# stlinkv2_1.net
KiCad netlist of a schematic drawn in Altium Designer
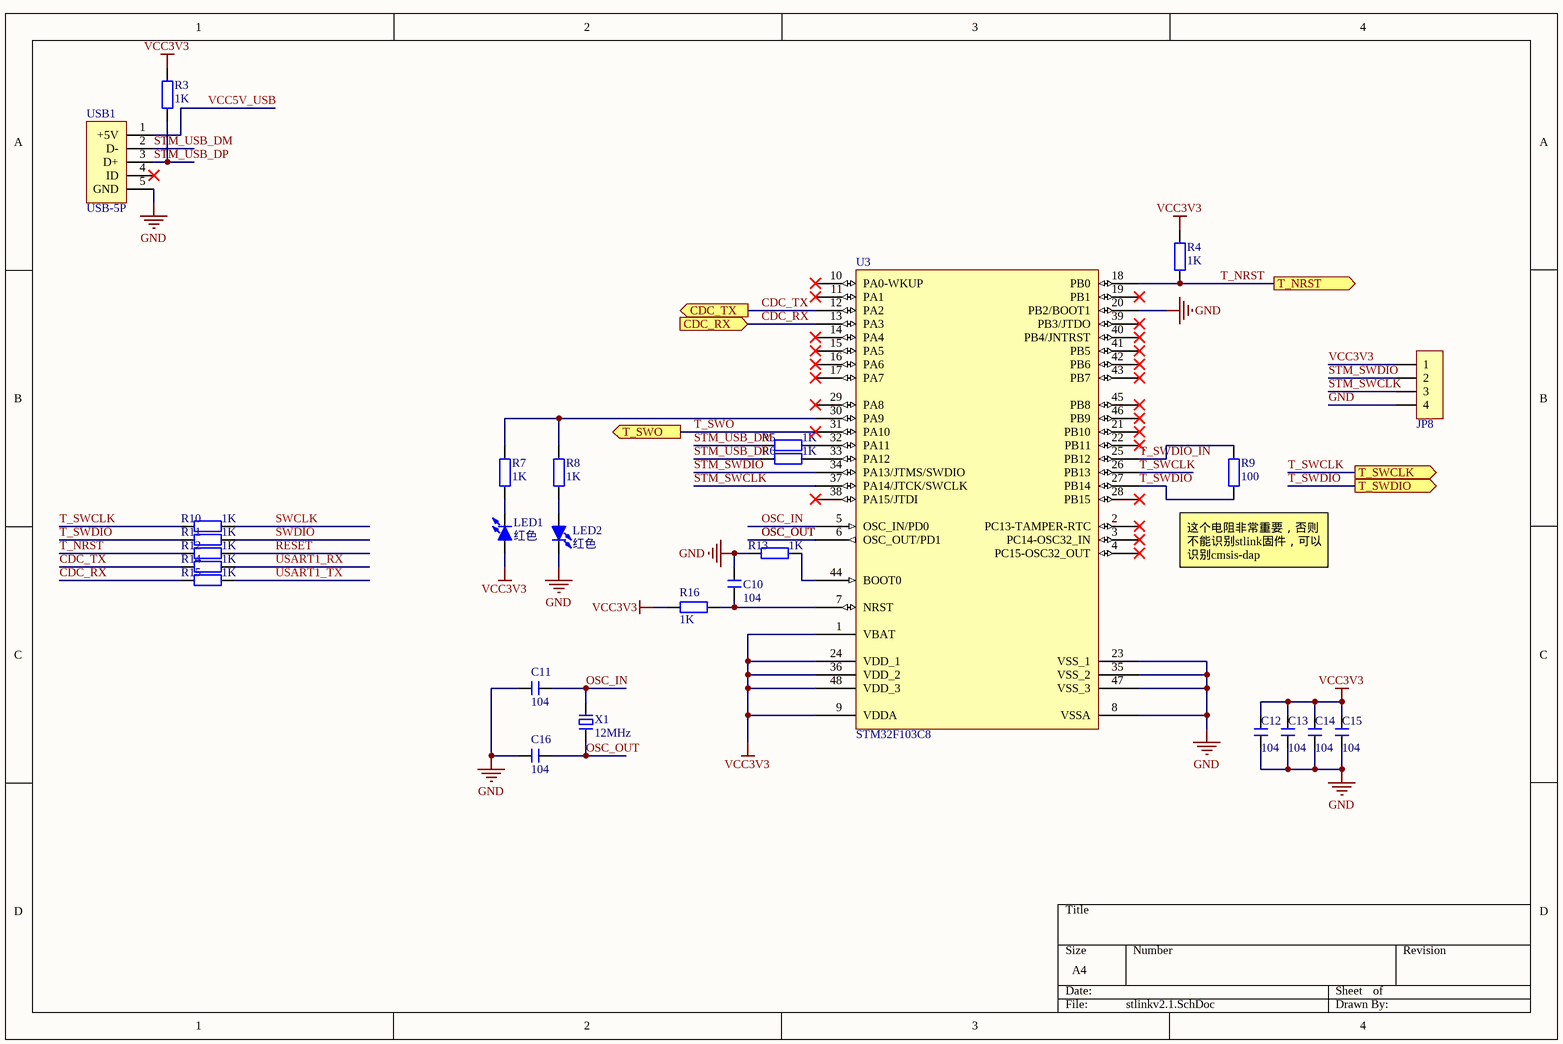
[diagram p0: stlinkv2.1.SchDoc]

(export (version "E")
  (design (tool "Eeschema 10.0.6"))
  (components
    (comp (ref "C10")
      (value "104")
      (footprint "C 0603_L")
      (description "无极性贴片电容")
      (fields (field (name "版权归属") "源创客"))
      (libsource (lib "3.1   - 电阻-电容-电感") (part "C"))
    )
    (comp (ref "C11")
      (value "104")
      (footprint "C 0603_L")
      (description "无极性贴片电容")
      (fields (field (name "版权归属") "源创客"))
      (libsource (lib "3.1   - 电阻-电容-电感") (part "C"))
    )
    (comp (ref "C12")
      (value "104")
      (footprint "C 0603_L")
      (description "无极性贴片电容")
      (fields (field (name "版权归属") "源创客"))
      (libsource (lib "3.1   - 电阻-电容-电感") (part "C"))
    )
    (comp (ref "C13")
      (value "104")
      (footprint "C 0603_L")
      (description "无极性贴片电容")
      (fields (field (name "版权归属") "源创客"))
      (libsource (lib "3.1   - 电阻-电容-电感") (part "C"))
    )
    (comp (ref "C14")
      (value "104")
      (footprint "C 0603_L")
      (description "无极性贴片电容")
      (fields (field (name "版权归属") "源创客"))
      (libsource (lib "3.1   - 电阻-电容-电感") (part "C"))
    )
    (comp (ref "C15")
      (value "104")
      (footprint "C 0603_L")
      (description "无极性贴片电容")
      (fields (field (name "版权归属") "源创客"))
      (libsource (lib "3.1   - 电阻-电容-电感") (part "C"))
    )
    (comp (ref "C16")
      (value "104")
      (footprint "C 0603_L")
      (description "无极性贴片电容")
      (fields (field (name "版权归属") "源创客"))
      (libsource (lib "3.1   - 电阻-电容-电感") (part "C"))
    )
    (comp (ref "JP8")
      (value "HDR-1X4")
      (footprint "HDR2.54-LI-4P")
      (description "4P接插件")
      (fields (field (name "版权归属") "源创客"))
      (libsource (lib "4.5   - 接插件-脚距2.54") (part "Header 4"))
    )
    (comp (ref "LED1")
      (value "红色")
      (footprint "LED 0603B")
      (description "贴片LED")
      (fields (field (name "版权归属") "源创客"))
      (libsource (lib "LED") (part "LED-SMD"))
    )
    (comp (ref "LED2")
      (value "红色")
      (footprint "LED 0603B")
      (description "贴片LED")
      (fields (field (name "版权归属") "源创客"))
      (libsource (lib "LED") (part "LED-SMD"))
    )
    (comp (ref "R3")
      (value "1K")
      (footprint "R 0603_L")
      (description "贴片电阻")
      (fields (field (name "版权归属") "源创客"))
      (libsource (lib "3.1   - 电阻-电容-电感") (part "R"))
    )
    (comp (ref "R4")
      (value "1K")
      (footprint "R 0603_L")
      (description "贴片电阻")
      (fields (field (name "版权归属") "源创客"))
      (libsource (lib "电阻-电容-电感") (part "R"))
    )
    (comp (ref "R5")
      (value "1K")
      (footprint "R 0603_L")
      (description "贴片电阻")
      (fields (field (name "版权归属") "源创客"))
      (libsource (lib "3.1   - 电阻-电容-电感") (part "R"))
    )
    (comp (ref "R6")
      (value "1K")
      (footprint "R 0603_L")
      (description "贴片电阻")
      (fields (field (name "版权归属") "源创客"))
      (libsource (lib "3.1   - 电阻-电容-电感") (part "R"))
    )
    (comp (ref "R7")
      (value "1K")
      (footprint "R 0603_L")
      (description "贴片电阻")
      (fields (field (name "版权归属") "源创客"))
      (libsource (lib "3.1   - 电阻-电容-电感") (part "R"))
    )
    (comp (ref "R8")
      (value "1K")
      (footprint "R 0603_L")
      (description "贴片电阻")
      (fields (field (name "版权归属") "源创客"))
      (libsource (lib "3.1   - 电阻-电容-电感") (part "R"))
    )
    (comp (ref "R9")
      (value "100")
      (footprint "R 0603_L")
      (description "贴片电阻")
      (fields (field (name "版权归属") "源创客"))
      (libsource (lib "3.1   - 电阻-电容-电感") (part "R"))
    )
    (comp (ref "R10")
      (value "1K")
      (footprint "R 0603_L")
      (description "贴片电阻")
      (fields (field (name "版权归属") "源创客"))
      (libsource (lib "3.1   - 电阻-电容-电感") (part "R"))
    )
    (comp (ref "R11")
      (value "1K")
      (footprint "R 0603_L")
      (description "贴片电阻")
      (fields (field (name "版权归属") "源创客"))
      (libsource (lib "3.1   - 电阻-电容-电感") (part "R"))
    )
    (comp (ref "R12")
      (value "1K")
      (footprint "R 0603_L")
      (description "贴片电阻")
      (fields (field (name "版权归属") "源创客"))
      (libsource (lib "3.1   - 电阻-电容-电感") (part "R"))
    )
    (comp (ref "R13")
      (value "1K")
      (footprint "R 0603_L")
      (description "贴片电阻")
      (fields (field (name "版权归属") "源创客"))
      (libsource (lib "3.1   - 电阻-电容-电感") (part "R"))
    )
    (comp (ref "R14")
      (value "1K")
      (footprint "R 0603_L")
      (description "贴片电阻")
      (fields (field (name "版权归属") "源创客"))
      (libsource (lib "3.1   - 电阻-电容-电感") (part "R"))
    )
    (comp (ref "R15")
      (value "1K")
      (footprint "R 0603_L")
      (description "贴片电阻")
      (fields (field (name "版权归属") "源创客"))
      (libsource (lib "3.1   - 电阻-电容-电感") (part "R"))
    )
    (comp (ref "R16")
      (value "1K")
      (footprint "R 0603_L")
      (description "贴片电阻")
      (fields (field (name "版权归属") "源创客"))
      (libsource (lib "3.1   - 电阻-电容-电感") (part "R"))
    )
    (comp (ref "U3")
      (value "STM32F103C8")
      (footprint "LQFP48 7X7_M")
      (description "Flaah:64/RAM:20/IO:36")
      (fields (field (name "版权归属") "源创客"))
      (libsource (lib "2.1   - STM32系列单片机") (part "STM32F103C8"))
    )
    (comp (ref "USB1")
      (value "USB-5P")
      (footprint "USB-MICRO_B")
      (description "微型USB母座")
      (fields (field (name "版权归属") "源创客"))
      (libsource (lib "4.1   - 接口类") (part "USB-5P"))
    )
    (comp (ref "X1")
      (value "12MHz")
      (footprint "OSC 5032-2P")
      (description "2脚无源脚晶振")
      (fields (field (name "版权归属") "源创客"))
      (libsource (lib "10.1 - 保险丝-晶振") (part "XTAL-2P"))
    )
  )
  (nets
    (net (code "1") (name "/CDC_RX") (class "Default")
      (node (ref "R15") (pin "2") (pinfunction "2_2") (pintype "passive"))
      (node (ref "U3") (pin "13") (pinfunction "PA3_13") (pintype "bidirectional"))
    )
    (net (code "2") (name "/CDC_TX") (class "Default")
      (node (ref "R14") (pin "2") (pinfunction "2_2") (pintype "passive"))
      (node (ref "U3") (pin "12") (pinfunction "PA2_12") (pintype "bidirectional"))
    )
    (net (code "3") (name "/OSC_IN") (class "Default")
      (node (ref "C11") (pin "2") (pinfunction "2_2") (pintype "passive"))
      (node (ref "U3") (pin "5") (pinfunction "OSC_IN/PD0_5") (pintype "input"))
      (node (ref "X1") (pin "2") (pinfunction "2_2") (pintype "passive"))
    )
    (net (code "4") (name "/OSC_OUT") (class "Default")
      (node (ref "C16") (pin "2") (pinfunction "2_2") (pintype "passive"))
      (node (ref "U3") (pin "6") (pinfunction "OSC_OUT/PD1_6") (pintype "output"))
      (node (ref "X1") (pin "1") (pinfunction "1_1") (pintype "passive"))
    )
    (net (code "5") (name "/RESET") (class "Default")
      (node (ref "R12") (pin "1") (pinfunction "1_1") (pintype "passive"))
    )
    (net (code "6") (name "/STM_SWCLK") (class "Default")
      (node (ref "JP8") (pin "3") (pinfunction "3_3") (pintype "passive"))
      (node (ref "U3") (pin "37") (pinfunction "PA14/JTCK/SWCLK_37") (pintype "bidirectional"))
    )
    (net (code "7") (name "/STM_SWDIO") (class "Default")
      (node (ref "JP8") (pin "2") (pinfunction "2_2") (pintype "passive"))
      (node (ref "U3") (pin "34") (pinfunction "PA13/JTMS/SWDIO_34") (pintype "bidirectional"))
    )
    (net (code "8") (name "/STM_USB_DM") (class "Default")
      (node (ref "R5") (pin "2") (pinfunction "2_2") (pintype "passive"))
      (node (ref "USB1") (pin "2") (pinfunction "D-_2") (pintype "passive"))
    )
    (net (code "9") (name "/STM_USB_DP") (class "Default")
      (node (ref "R3") (pin "2") (pinfunction "2_2") (pintype "passive"))
      (node (ref "R6") (pin "2") (pinfunction "2_2") (pintype "passive"))
      (node (ref "USB1") (pin "3") (pinfunction "D+_3") (pintype "passive"))
    )
    (net (code "10") (name "/SWCLK") (class "Default")
      (node (ref "R10") (pin "1") (pinfunction "1_1") (pintype "passive"))
    )
    (net (code "11") (name "/SWDIO") (class "Default")
      (node (ref "R11") (pin "1") (pinfunction "1_1") (pintype "passive"))
    )
    (net (code "12") (name "/T_NRST") (class "Default")
      (node (ref "R12") (pin "2") (pinfunction "2_2") (pintype "passive"))
      (node (ref "R4") (pin "1") (pinfunction "1_1") (pintype "passive"))
      (node (ref "U3") (pin "18") (pinfunction "PB0_18") (pintype "bidirectional"))
    )
    (net (code "13") (name "/T_SWCLK") (class "Default")
      (node (ref "R10") (pin "2") (pinfunction "2_2") (pintype "passive"))
      (node (ref "U3") (pin "26") (pinfunction "PB13_26") (pintype "bidirectional"))
    )
    (net (code "14") (name "/T_SWDIO") (class "Default")
      (node (ref "R11") (pin "2") (pinfunction "2_2") (pintype "passive"))
      (node (ref "R9") (pin "1") (pinfunction "1_1") (pintype "passive"))
      (node (ref "U3") (pin "27") (pinfunction "PB14_27") (pintype "bidirectional"))
    )
    (net (code "15") (name "/T_SWDIO_IN") (class "Default")
      (node (ref "R9") (pin "2") (pinfunction "2_2") (pintype "passive"))
      (node (ref "U3") (pin "25") (pinfunction "PB12_25") (pintype "bidirectional"))
    )
    (net (code "16") (name "/T_SWO") (class "Default")
      (node (ref "U3") (pin "31") (pinfunction "PA10_31") (pintype "bidirectional+no_connect"))
    )
    (net (code "17") (name "/USART1_RX") (class "Default")
      (node (ref "R14") (pin "1") (pinfunction "1_1") (pintype "passive"))
    )
    (net (code "18") (name "/USART1_TX") (class "Default")
      (node (ref "R15") (pin "1") (pinfunction "1_1") (pintype "passive"))
    )
    (net (code "19") (name "/VCC5V_USB") (class "Default")
      (node (ref "USB1") (pin "1") (pinfunction "+5V_1") (pintype "passive"))
    )
    (net (code "20") (name "GND") (class "Default")
      (node (ref "C10") (pin "1") (pinfunction "1_1") (pintype "passive"))
      (node (ref "C11") (pin "1") (pinfunction "1_1") (pintype "passive"))
      (node (ref "C12") (pin "2") (pinfunction "2_2") (pintype "passive"))
      (node (ref "C13") (pin "2") (pinfunction "2_2") (pintype "passive"))
      (node (ref "C14") (pin "2") (pinfunction "2_2") (pintype "passive"))
      (node (ref "C15") (pin "2") (pinfunction "2_2") (pintype "passive"))
      (node (ref "C16") (pin "1") (pinfunction "1_1") (pintype "passive"))
      (node (ref "JP8") (pin "4") (pinfunction "4_4") (pintype "passive"))
      (node (ref "LED2") (pin "2") (pinfunction "K_2") (pintype "passive"))
      (node (ref "R13") (pin "2") (pinfunction "2_2") (pintype "passive"))
      (node (ref "U3") (pin "20") (pinfunction "PB2/BOOT1_20") (pintype "bidirectional"))
      (node (ref "U3") (pin "23") (pinfunction "VSS_1_23") (pintype "power_in"))
      (node (ref "U3") (pin "35") (pinfunction "VSS_2_35") (pintype "power_in"))
      (node (ref "U3") (pin "47") (pinfunction "VSS_3_47") (pintype "power_in"))
      (node (ref "U3") (pin "8") (pinfunction "VSSA_8") (pintype "power_in"))
      (node (ref "USB1") (pin "5") (pinfunction "GND_5") (pintype "passive"))
    )
    (net (code "21") (name "Net-(LED1-K)") (class "Default")
      (node (ref "LED1") (pin "2") (pinfunction "K_2") (pintype "passive"))
      (node (ref "R7") (pin "1") (pinfunction "1_1") (pintype "passive"))
    )
    (net (code "22") (name "Net-(LED2-A)") (class "Default")
      (node (ref "LED2") (pin "1") (pinfunction "A_1") (pintype "passive"))
      (node (ref "R8") (pin "1") (pinfunction "1_1") (pintype "passive"))
    )
    (net (code "23") (name "Net-(U3-BOOT0)") (class "Default")
      (node (ref "R13") (pin "1") (pinfunction "1_1") (pintype "passive"))
      (node (ref "U3") (pin "44") (pinfunction "BOOT0_44") (pintype "input"))
    )
    (net (code "24") (name "Net-(U3-NRST)") (class "Default")
      (node (ref "C10") (pin "2") (pinfunction "2_2") (pintype "passive"))
      (node (ref "R16") (pin "1") (pinfunction "1_1") (pintype "passive"))
      (node (ref "U3") (pin "7") (pinfunction "NRST_7") (pintype "bidirectional"))
    )
    (net (code "25") (name "Net-(U3-PA9)") (class "Default")
      (node (ref "R7") (pin "2") (pinfunction "2_2") (pintype "passive"))
      (node (ref "R8") (pin "2") (pinfunction "2_2") (pintype "passive"))
      (node (ref "U3") (pin "30") (pinfunction "PA9_30") (pintype "bidirectional"))
    )
    (net (code "26") (name "Net-(U3-PA11)") (class "Default")
      (node (ref "R5") (pin "1") (pinfunction "1_1") (pintype "passive"))
      (node (ref "U3") (pin "32") (pinfunction "PA11_32") (pintype "bidirectional"))
    )
    (net (code "27") (name "Net-(U3-PA12)") (class "Default")
      (node (ref "R6") (pin "1") (pinfunction "1_1") (pintype "passive"))
      (node (ref "U3") (pin "33") (pinfunction "PA12_33") (pintype "bidirectional"))
    )
    (net (code "28") (name "VCC3V3") (class "Default")
      (node (ref "C12") (pin "1") (pinfunction "1_1") (pintype "passive"))
      (node (ref "C13") (pin "1") (pinfunction "1_1") (pintype "passive"))
      (node (ref "C14") (pin "1") (pinfunction "1_1") (pintype "passive"))
      (node (ref "C15") (pin "1") (pinfunction "1_1") (pintype "passive"))
      (node (ref "JP8") (pin "1") (pinfunction "1_1") (pintype "passive"))
      (node (ref "LED1") (pin "1") (pinfunction "A_1") (pintype "passive"))
      (node (ref "R16") (pin "2") (pinfunction "2_2") (pintype "passive"))
      (node (ref "R3") (pin "1") (pinfunction "1_1") (pintype "passive"))
      (node (ref "R4") (pin "2") (pinfunction "2_2") (pintype "passive"))
      (node (ref "U3") (pin "1") (pinfunction "VBAT_1") (pintype "power_in"))
      (node (ref "U3") (pin "24") (pinfunction "VDD_1_24") (pintype "power_in"))
      (node (ref "U3") (pin "36") (pinfunction "VDD_2_36") (pintype "power_in"))
      (node (ref "U3") (pin "48") (pinfunction "VDD_3_48") (pintype "power_in"))
      (node (ref "U3") (pin "9") (pinfunction "VDDA_9") (pintype "power_in"))
    )
    (net (code "29") (name "unconnected-(U3-PA0-WKUP-Pad10)") (class "Default")
      (node (ref "U3") (pin "10") (pinfunction "PA0-WKUP_10") (pintype "bidirectional+no_connect"))
    )
    (net (code "30") (name "unconnected-(U3-PA1-Pad11)") (class "Default")
      (node (ref "U3") (pin "11") (pinfunction "PA1_11") (pintype "bidirectional+no_connect"))
    )
    (net (code "31") (name "unconnected-(U3-PA4-Pad14)") (class "Default")
      (node (ref "U3") (pin "14") (pinfunction "PA4_14") (pintype "bidirectional+no_connect"))
    )
    (net (code "32") (name "unconnected-(U3-PA5-Pad15)") (class "Default")
      (node (ref "U3") (pin "15") (pinfunction "PA5_15") (pintype "bidirectional+no_connect"))
    )
    (net (code "33") (name "unconnected-(U3-PA6-Pad16)") (class "Default")
      (node (ref "U3") (pin "16") (pinfunction "PA6_16") (pintype "bidirectional+no_connect"))
    )
    (net (code "34") (name "unconnected-(U3-PA7-Pad17)") (class "Default")
      (node (ref "U3") (pin "17") (pinfunction "PA7_17") (pintype "bidirectional+no_connect"))
    )
    (net (code "35") (name "unconnected-(U3-PA8-Pad29)") (class "Default")
      (node (ref "U3") (pin "29") (pinfunction "PA8_29") (pintype "bidirectional+no_connect"))
    )
    (net (code "36") (name "unconnected-(U3-PA15{slash}JTDI-Pad38)") (class "Default")
      (node (ref "U3") (pin "38") (pinfunction "PA15/JTDI_38") (pintype "bidirectional+no_connect"))
    )
    (net (code "37") (name "unconnected-(U3-PB1-Pad19)") (class "Default")
      (node (ref "U3") (pin "19") (pinfunction "PB1_19") (pintype "bidirectional+no_connect"))
    )
    (net (code "38") (name "unconnected-(U3-PB3{slash}JTDO-Pad39)") (class "Default")
      (node (ref "U3") (pin "39") (pinfunction "PB3/JTDO_39") (pintype "bidirectional+no_connect"))
    )
    (net (code "39") (name "unconnected-(U3-PB4{slash}JNTRST-Pad40)") (class "Default")
      (node (ref "U3") (pin "40") (pinfunction "PB4/JNTRST_40") (pintype "bidirectional+no_connect"))
    )
    (net (code "40") (name "unconnected-(U3-PB5-Pad41)") (class "Default")
      (node (ref "U3") (pin "41") (pinfunction "PB5_41") (pintype "bidirectional+no_connect"))
    )
    (net (code "41") (name "unconnected-(U3-PB6-Pad42)") (class "Default")
      (node (ref "U3") (pin "42") (pinfunction "PB6_42") (pintype "bidirectional+no_connect"))
    )
    (net (code "42") (name "unconnected-(U3-PB7-Pad43)") (class "Default")
      (node (ref "U3") (pin "43") (pinfunction "PB7_43") (pintype "bidirectional+no_connect"))
    )
    (net (code "43") (name "unconnected-(U3-PB8-Pad45)") (class "Default")
      (node (ref "U3") (pin "45") (pinfunction "PB8_45") (pintype "bidirectional+no_connect"))
    )
    (net (code "44") (name "unconnected-(U3-PB9-Pad46)") (class "Default")
      (node (ref "U3") (pin "46") (pinfunction "PB9_46") (pintype "bidirectional+no_connect"))
    )
    (net (code "45") (name "unconnected-(U3-PB10-Pad21)") (class "Default")
      (node (ref "U3") (pin "21") (pinfunction "PB10_21") (pintype "bidirectional+no_connect"))
    )
    (net (code "46") (name "unconnected-(U3-PB11-Pad22)") (class "Default")
      (node (ref "U3") (pin "22") (pinfunction "PB11_22") (pintype "bidirectional+no_connect"))
    )
    (net (code "47") (name "unconnected-(U3-PB15-Pad28)") (class "Default")
      (node (ref "U3") (pin "28") (pinfunction "PB15_28") (pintype "bidirectional+no_connect"))
    )
    (net (code "48") (name "unconnected-(U3-PC13-TAMPER-RTC-Pad2)") (class "Default")
      (node (ref "U3") (pin "2") (pinfunction "PC13-TAMPER-RTC_2") (pintype "bidirectional+no_connect"))
    )
    (net (code "49") (name "unconnected-(U3-PC14-OSC32_IN-Pad3)") (class "Default")
      (node (ref "U3") (pin "3") (pinfunction "PC14-OSC32_IN_3") (pintype "bidirectional+no_connect"))
    )
    (net (code "50") (name "unconnected-(U3-PC15-OSC32_OUT-Pad4)") (class "Default")
      (node (ref "U3") (pin "4") (pinfunction "PC15-OSC32_OUT_4") (pintype "bidirectional+no_connect"))
    )
    (net (code "51") (name "unconnected-(USB1-ID-Pad4)") (class "Default")
      (node (ref "USB1") (pin "4") (pinfunction "ID_4") (pintype "passive+no_connect"))
    )
  )
)
